# MC33886_PowerModule.net
KiCad netlist of a schematic drawn in Altium Designer
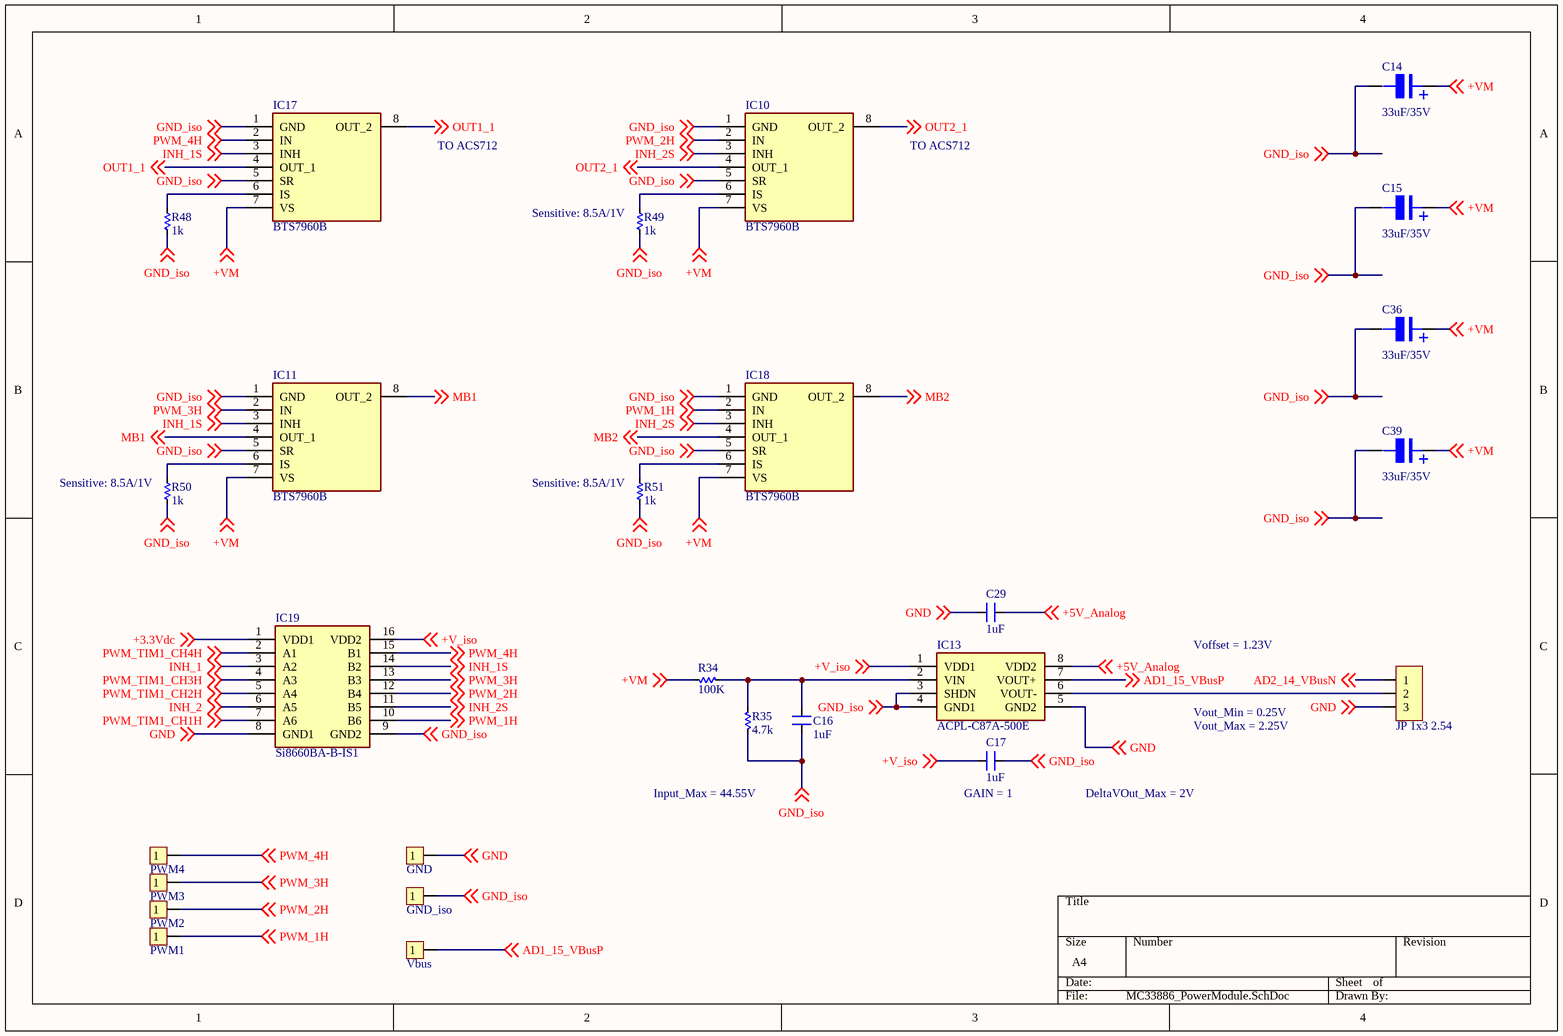
[diagram p0: MC33886_PowerModule.SchDoc]

(export (version "E")
  (design (tool "Eeschema 10.0.6"))
  (components
    (comp (ref "C14")
      (value "33uF/35V")
      (footprint "tu nhom 8 (e)")
      (description "Dán")
      (libsource (lib "Tu dien") (part "Tu Nhom 33uF 35V"))
    )
    (comp (ref "C15")
      (value "33uF/35V")
      (footprint "tu nhom 8 (e)")
      (description "Dán")
      (libsource (lib "Tu dien") (part "Tu Nhom 33uF 35V"))
    )
    (comp (ref "C16")
      (value "1uF")
      (footprint "Arduino_PLC_PCB:CM-0805 capacitor")
      (description "0805_SMD_20pF")
      (libsource (lib "Arduino_PLC_SchLib") (part "CN"))
    )
    (comp (ref "C17")
      (value "1uF")
      (footprint "Arduino_PLC_PCB:CM-0805 capacitor")
      (description "0805_SMD_20pF")
      (libsource (lib "Arduino_PLC_SchLib") (part "CN"))
    )
    (comp (ref "C29")
      (value "1uF")
      (footprint "Arduino_PLC_PCB:CM-0805 capacitor")
      (description "0805_SMD_20pF")
      (libsource (lib "Arduino_PLC_SchLib") (part "CN"))
    )
    (comp (ref "C36")
      (value "33uF/35V")
      (footprint "tu nhom 8 (e)")
      (description "Dán")
      (libsource (lib "Tu dien") (part "Tu Nhom 33uF 35V"))
    )
    (comp (ref "C39")
      (value "33uF/35V")
      (footprint "tu nhom 8 (e)")
      (description "Dán")
      (libsource (lib "Tu dien") (part "Tu Nhom 33uF 35V"))
    )
    (comp (ref "GND")
      (value "GND")
      (footprint "JP 1x1 DT")
      (description "Cắm")
      (libsource (lib "Jump") (part "JP 1x1 2.54 Duc Cong"))
    )
    (comp (ref "GND_iso")
      (value "GND_iso")
      (footprint "JP 1x1 DT")
      (description "Cắm")
      (libsource (lib "Jump") (part "JP 1x1 2.54 Duc Cong"))
    )
    (comp (ref "IC10")
      (value "BTS7960B")
      (footprint "BTS7960B")
      (description "Integrated Circuit")
      (libsource (lib "SamacSys") (part "BTS7960B"))
    )
    (comp (ref "IC11")
      (value "BTS7960B")
      (footprint "BTS7960B")
      (description "Integrated Circuit")
      (libsource (lib "SamacSys") (part "BTS7960B"))
    )
    (comp (ref "IC13")
      (value "ACPL-C87A-500E")
      (footprint "SamacSys:SOIC127P1150X361-8N")
      (description "Integrated Circuit")
      (fields (field (name "MOUSER PART NUMBER") "630-ACPL-C87A-500E"))
      (libsource (lib "*") (part "ACPL-C87A-500E"))
    )
    (comp (ref "IC17")
      (value "BTS7960B")
      (footprint "BTS7960B")
      (description "Integrated Circuit")
      (libsource (lib "SamacSys") (part "BTS7960B"))
    )
    (comp (ref "IC18")
      (value "BTS7960B")
      (footprint "BTS7960B")
      (description "Integrated Circuit")
      (libsource (lib "SamacSys") (part "BTS7960B"))
    )
    (comp (ref "IC19")
      (value "Si8660BA-B-IS1")
      (footprint "SOIC127P600X175-16N")
      (description "Integrated Circuit")
      (fields (field (name "MOUSER PART NUMBER") "634-SI8660BA-B-IS1"))
      (libsource (lib "SamacSys") (part "Si8660BA-B-IS1"))
    )
    (comp (ref "JP3")
      (value "JP 1x3 2.54")
      (footprint "JP 1x3 DT")
      (description "Cắm")
      (libsource (lib "Jump") (part "JP 1x3 2.54 Duc Thang"))
    )
    (comp (ref "PWM1")
      (value "PWM1")
      (footprint "JP 1x1 DT")
      (description "Cắm")
      (libsource (lib "") (part "JP 1x1 2.54 Duc Cong_1"))
    )
    (comp (ref "PWM2")
      (value "PWM2")
      (footprint "JP 1x1 DT")
      (description "Cắm")
      (libsource (lib "") (part "JP 1x1 2.54 Duc Cong_1"))
    )
    (comp (ref "PWM3")
      (value "PWM3")
      (footprint "JP 1x1 DT")
      (description "Cắm")
      (libsource (lib "") (part "JP 1x1 2.54 Duc Cong_1"))
    )
    (comp (ref "PWM4")
      (value "PWM4")
      (footprint "JP 1x1 DT")
      (description "Cắm")
      (libsource (lib "") (part "JP 1x1 2.54 Duc Cong_1"))
    )
    (comp (ref "R34")
      (value "100K")
      (footprint "RES-SMD-0805")
      (description "Resistor")
      (fields
        (field (name "MANUFACTURER") "Generic Components")
        (field (name "PUBLISHER") "Altium Hobart Technology Centre")
      )
      (libsource (lib "LIBRARY") (part "Res-SMD"))
    )
    (comp (ref "R35")
      (value "4.7k")
      (footprint "RES-SMD-0805")
      (description "Resistor")
      (fields
        (field (name "MANUFACTURER") "Generic Components")
        (field (name "PUBLISHER") "Altium Hobart Technology Centre")
      )
      (libsource (lib "LIBRARY") (part "Res-SMD"))
    )
    (comp (ref "R48")
      (value "1k")
      (footprint "RES-SMD-0805")
      (description "Resistor")
      (fields
        (field (name "MANUFACTURER") "Generic Components")
        (field (name "PUBLISHER") "Altium Hobart Technology Centre")
      )
      (libsource (lib "LIBRARY") (part "Res-SMD"))
    )
    (comp (ref "R49")
      (value "1k")
      (footprint "RES-SMD-0805")
      (description "Resistor")
      (fields
        (field (name "MANUFACTURER") "Generic Components")
        (field (name "PUBLISHER") "Altium Hobart Technology Centre")
      )
      (libsource (lib "LIBRARY") (part "Res-SMD"))
    )
    (comp (ref "R50")
      (value "1k")
      (footprint "RES-SMD-0805")
      (description "Resistor")
      (fields
        (field (name "MANUFACTURER") "Generic Components")
        (field (name "PUBLISHER") "Altium Hobart Technology Centre")
      )
      (libsource (lib "LIBRARY") (part "Res-SMD"))
    )
    (comp (ref "R51")
      (value "1k")
      (footprint "RES-SMD-0805")
      (description "Resistor")
      (fields
        (field (name "MANUFACTURER") "Generic Components")
        (field (name "PUBLISHER") "Altium Hobart Technology Centre")
      )
      (libsource (lib "LIBRARY") (part "Res-SMD"))
    )
    (comp (ref "Vbus")
      (value "Vbus")
      (footprint "JP 1x1 DT")
      (description "Cắm")
      (libsource (lib "Jump") (part "JP 1x1 2.54 Duc Cong"))
    )
  )
  (nets
    (net (code "1") (name "+3.3Vdc") (class "Default")
      (node (ref "IC19") (pin "1") (pinfunction "VDD1_1") (pintype "passive"))
    )
    (net (code "2") (name "+5V_Analog") (class "Default")
      (node (ref "C29") (pin "1") (pinfunction "1_1") (pintype "passive"))
      (node (ref "IC13") (pin "8") (pinfunction "VDD2_8") (pintype "passive"))
    )
    (net (code "3") (name "+VM") (class "Default")
      (node (ref "C14") (pin "1") (pinfunction "1_1") (pintype "passive"))
      (node (ref "C15") (pin "1") (pinfunction "1_1") (pintype "passive"))
      (node (ref "C36") (pin "1") (pinfunction "1_1") (pintype "passive"))
      (node (ref "C39") (pin "1") (pinfunction "1_1") (pintype "passive"))
      (node (ref "IC10") (pin "7") (pinfunction "VS_7") (pintype "passive"))
      (node (ref "IC11") (pin "7") (pinfunction "VS_7") (pintype "passive"))
      (node (ref "IC17") (pin "7") (pinfunction "VS_7") (pintype "passive"))
      (node (ref "IC18") (pin "7") (pinfunction "VS_7") (pintype "passive"))
      (node (ref "R34") (pin "1") (pinfunction "1_1") (pintype "passive"))
    )
    (net (code "4") (name "+V_iso") (class "Default")
      (node (ref "C17") (pin "1") (pinfunction "1_1") (pintype "passive"))
      (node (ref "IC13") (pin "1") (pinfunction "VDD1_1") (pintype "passive"))
      (node (ref "IC19") (pin "16") (pinfunction "VDD2_16") (pintype "passive"))
    )
    (net (code "5") (name "AD1_15_VBusP") (class "Default")
      (node (ref "IC13") (pin "7") (pinfunction "VOUT+_7") (pintype "passive"))
      (node (ref "Vbus") (pin "1") (pinfunction "1_1") (pintype "passive"))
    )
    (net (code "6") (name "AD2_14_VBusN") (class "Default")
      (node (ref "JP3") (pin "1") (pinfunction "1_1") (pintype "passive"))
    )
    (net (code "7") (name "GND") (class "Default")
      (node (ref "C29") (pin "2") (pinfunction "2_2") (pintype "passive"))
      (node (ref "GND") (pin "1") (pinfunction "1_1") (pintype "passive"))
      (node (ref "IC13") (pin "5") (pinfunction "GND2_5") (pintype "passive"))
      (node (ref "IC19") (pin "8") (pinfunction "GND1_8") (pintype "passive"))
      (node (ref "JP3") (pin "3") (pinfunction "3_3") (pintype "passive"))
    )
    (net (code "8") (name "GND_iso") (class "Default")
      (node (ref "C14") (pin "2") (pinfunction "2_2") (pintype "passive"))
      (node (ref "C15") (pin "2") (pinfunction "2_2") (pintype "passive"))
      (node (ref "C16") (pin "2") (pinfunction "2_2") (pintype "passive"))
      (node (ref "C17") (pin "2") (pinfunction "2_2") (pintype "passive"))
      (node (ref "C36") (pin "2") (pinfunction "2_2") (pintype "passive"))
      (node (ref "C39") (pin "2") (pinfunction "2_2") (pintype "passive"))
      (node (ref "GND_iso") (pin "1") (pinfunction "1_1") (pintype "passive"))
      (node (ref "IC10") (pin "1") (pinfunction "GND_1") (pintype "passive"))
      (node (ref "IC10") (pin "5") (pinfunction "SR_5") (pintype "passive"))
      (node (ref "IC11") (pin "1") (pinfunction "GND_1") (pintype "passive"))
      (node (ref "IC11") (pin "5") (pinfunction "SR_5") (pintype "passive"))
      (node (ref "IC13") (pin "3") (pinfunction "SHDN_3") (pintype "passive"))
      (node (ref "IC13") (pin "4") (pinfunction "GND1_4") (pintype "passive"))
      (node (ref "IC17") (pin "1") (pinfunction "GND_1") (pintype "passive"))
      (node (ref "IC17") (pin "5") (pinfunction "SR_5") (pintype "passive"))
      (node (ref "IC18") (pin "1") (pinfunction "GND_1") (pintype "passive"))
      (node (ref "IC18") (pin "5") (pinfunction "SR_5") (pintype "passive"))
      (node (ref "IC19") (pin "9") (pinfunction "GND2_9") (pintype "passive"))
      (node (ref "R35") (pin "2") (pinfunction "2_2") (pintype "passive"))
      (node (ref "R48") (pin "2") (pinfunction "2_2") (pintype "passive"))
      (node (ref "R49") (pin "2") (pinfunction "2_2") (pintype "passive"))
      (node (ref "R50") (pin "2") (pinfunction "2_2") (pintype "passive"))
      (node (ref "R51") (pin "2") (pinfunction "2_2") (pintype "passive"))
    )
    (net (code "9") (name "INH_1") (class "Default")
      (node (ref "IC19") (pin "3") (pinfunction "A2_3") (pintype "passive"))
    )
    (net (code "10") (name "INH_1S") (class "Default")
      (node (ref "IC11") (pin "3") (pinfunction "INH_3") (pintype "passive"))
      (node (ref "IC17") (pin "3") (pinfunction "INH_3") (pintype "passive"))
      (node (ref "IC19") (pin "14") (pinfunction "B2_14") (pintype "passive"))
    )
    (net (code "11") (name "INH_2") (class "Default")
      (node (ref "IC19") (pin "6") (pinfunction "A5_6") (pintype "passive"))
    )
    (net (code "12") (name "INH_2S") (class "Default")
      (node (ref "IC10") (pin "3") (pinfunction "INH_3") (pintype "passive"))
      (node (ref "IC18") (pin "3") (pinfunction "INH_3") (pintype "passive"))
      (node (ref "IC19") (pin "11") (pinfunction "B5_11") (pintype "passive"))
    )
    (net (code "13") (name "MB1") (class "Default")
      (node (ref "IC11") (pin "4") (pinfunction "OUT_1_4") (pintype "passive"))
      (node (ref "IC11") (pin "8") (pinfunction "OUT_2_8") (pintype "passive"))
    )
    (net (code "14") (name "MB2") (class "Default")
      (node (ref "IC18") (pin "4") (pinfunction "OUT_1_4") (pintype "passive"))
      (node (ref "IC18") (pin "8") (pinfunction "OUT_2_8") (pintype "passive"))
    )
    (net (code "15") (name "Net-(IC10-IS)") (class "Default")
      (node (ref "IC10") (pin "6") (pinfunction "IS_6") (pintype "passive"))
      (node (ref "R49") (pin "1") (pinfunction "1_1") (pintype "passive"))
    )
    (net (code "16") (name "Net-(IC11-IS)") (class "Default")
      (node (ref "IC11") (pin "6") (pinfunction "IS_6") (pintype "passive"))
      (node (ref "R50") (pin "1") (pinfunction "1_1") (pintype "passive"))
    )
    (net (code "17") (name "Net-(IC13-VIN)") (class "Default")
      (node (ref "C16") (pin "1") (pinfunction "1_1") (pintype "passive"))
      (node (ref "IC13") (pin "2") (pinfunction "VIN_2") (pintype "passive"))
      (node (ref "R34") (pin "2") (pinfunction "2_2") (pintype "passive"))
      (node (ref "R35") (pin "1") (pinfunction "1_1") (pintype "passive"))
    )
    (net (code "18") (name "Net-(IC13-VOUT-)") (class "Default")
      (node (ref "IC13") (pin "6") (pinfunction "VOUT-_6") (pintype "passive"))
      (node (ref "JP3") (pin "2") (pinfunction "2_2") (pintype "passive"))
    )
    (net (code "19") (name "Net-(IC17-IS)") (class "Default")
      (node (ref "IC17") (pin "6") (pinfunction "IS_6") (pintype "passive"))
      (node (ref "R48") (pin "1") (pinfunction "1_1") (pintype "passive"))
    )
    (net (code "20") (name "Net-(IC18-IS)") (class "Default")
      (node (ref "IC18") (pin "6") (pinfunction "IS_6") (pintype "passive"))
      (node (ref "R51") (pin "1") (pinfunction "1_1") (pintype "passive"))
    )
    (net (code "21") (name "OUT1_1") (class "Default")
      (node (ref "IC17") (pin "4") (pinfunction "OUT_1_4") (pintype "passive"))
      (node (ref "IC17") (pin "8") (pinfunction "OUT_2_8") (pintype "passive"))
    )
    (net (code "22") (name "OUT2_1") (class "Default")
      (node (ref "IC10") (pin "4") (pinfunction "OUT_1_4") (pintype "passive"))
      (node (ref "IC10") (pin "8") (pinfunction "OUT_2_8") (pintype "passive"))
    )
    (net (code "23") (name "PWM_1H") (class "Default")
      (node (ref "IC18") (pin "2") (pinfunction "IN_2") (pintype "passive"))
      (node (ref "IC19") (pin "10") (pinfunction "B6_10") (pintype "passive"))
      (node (ref "PWM1") (pin "1") (pinfunction "1_1") (pintype "passive"))
    )
    (net (code "24") (name "PWM_2H") (class "Default")
      (node (ref "IC10") (pin "2") (pinfunction "IN_2") (pintype "passive"))
      (node (ref "IC19") (pin "12") (pinfunction "B4_12") (pintype "passive"))
      (node (ref "PWM2") (pin "1") (pinfunction "1_1") (pintype "passive"))
    )
    (net (code "25") (name "PWM_3H") (class "Default")
      (node (ref "IC11") (pin "2") (pinfunction "IN_2") (pintype "passive"))
      (node (ref "IC19") (pin "13") (pinfunction "B3_13") (pintype "passive"))
      (node (ref "PWM3") (pin "1") (pinfunction "1_1") (pintype "passive"))
    )
    (net (code "26") (name "PWM_4H") (class "Default")
      (node (ref "IC17") (pin "2") (pinfunction "IN_2") (pintype "passive"))
      (node (ref "IC19") (pin "15") (pinfunction "B1_15") (pintype "passive"))
      (node (ref "PWM4") (pin "1") (pinfunction "1_1") (pintype "passive"))
    )
    (net (code "27") (name "PWM_TIM1_CH1H") (class "Default")
      (node (ref "IC19") (pin "7") (pinfunction "A6_7") (pintype "passive"))
    )
    (net (code "28") (name "PWM_TIM1_CH2H") (class "Default")
      (node (ref "IC19") (pin "5") (pinfunction "A4_5") (pintype "passive"))
    )
    (net (code "29") (name "PWM_TIM1_CH3H") (class "Default")
      (node (ref "IC19") (pin "4") (pinfunction "A3_4") (pintype "passive"))
    )
    (net (code "30") (name "PWM_TIM1_CH4H") (class "Default")
      (node (ref "IC19") (pin "2") (pinfunction "A1_2") (pintype "passive"))
    )
  )
)
